# Quadcopter.net
KiCad netlist of a schematic drawn in EAGLE
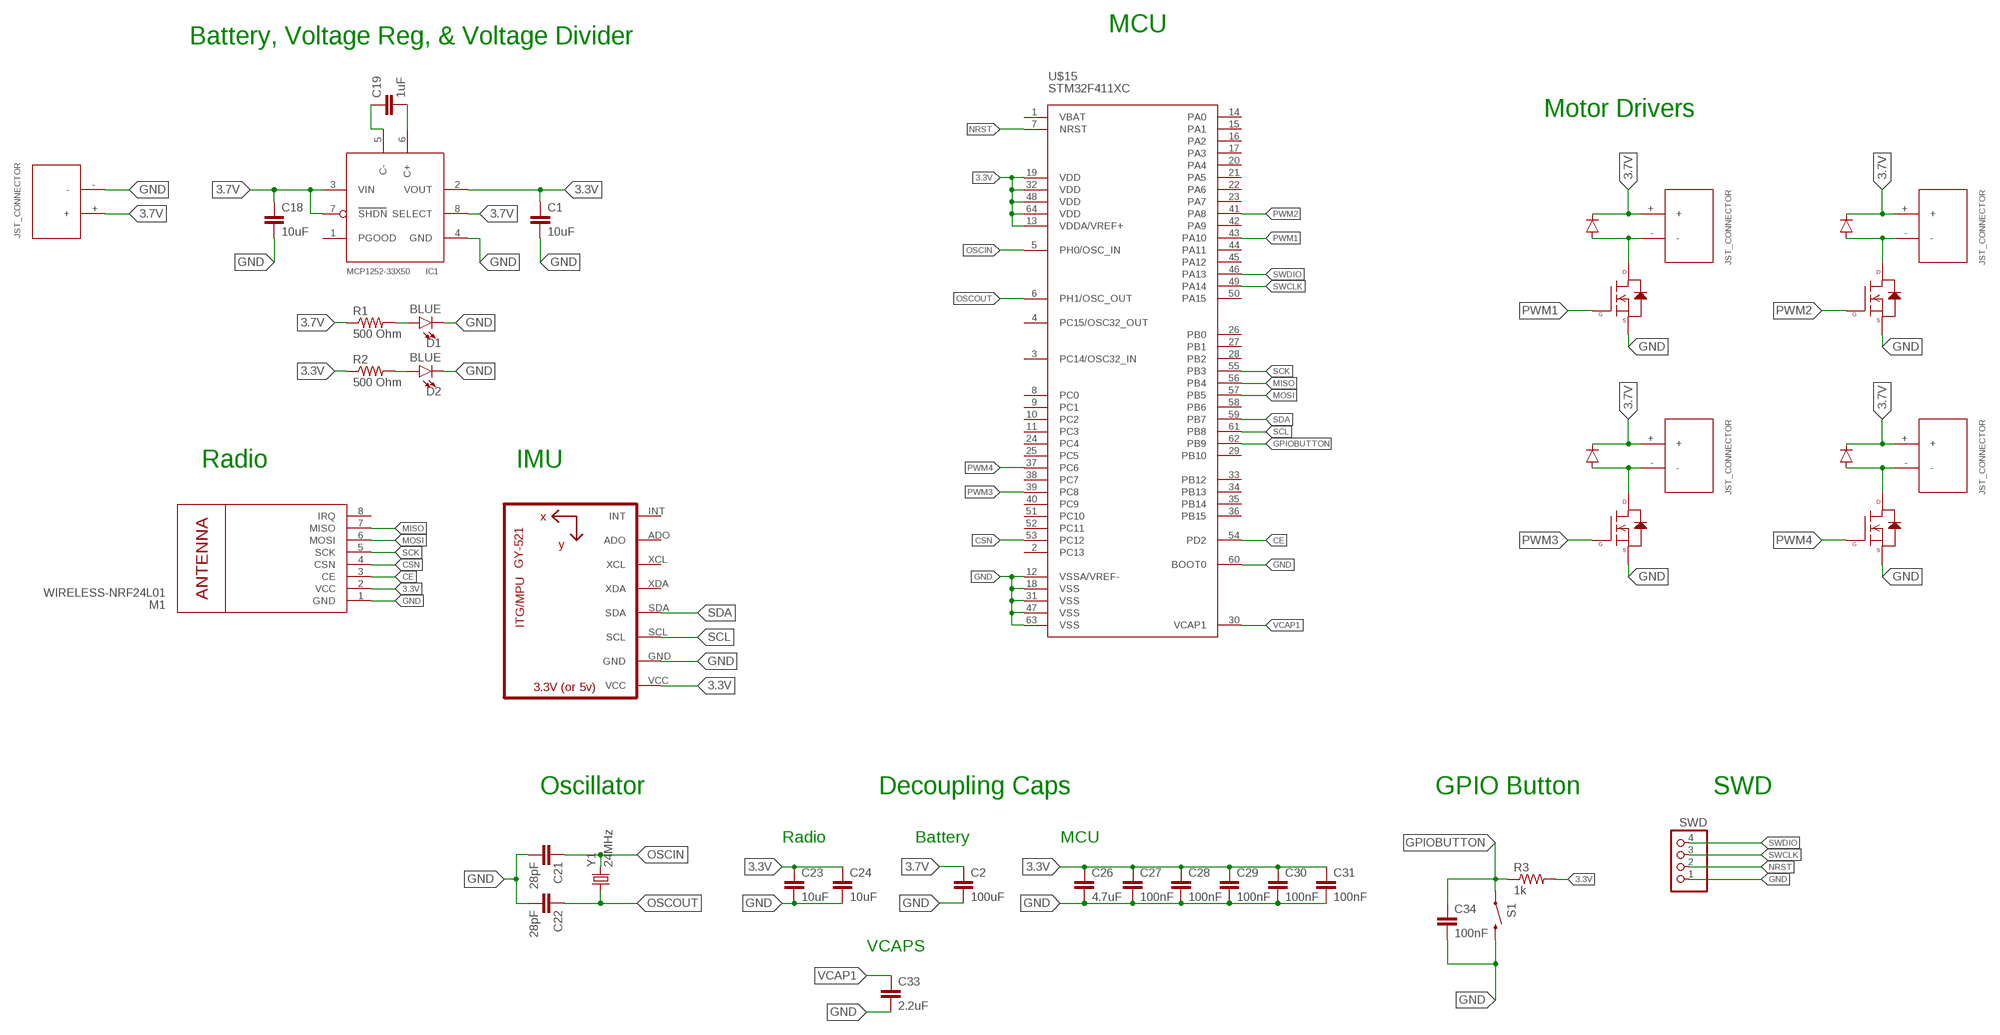
[diagram p0: schematic, sheet 1]

(export (version "E")
  (design (tool "Eeschema 10.0.6"))
  (components
    (comp (ref "C1")
      (value "10uF")
      (footprint "eagle-import:C0402K")
      (libsource (lib "eagle-import") (part "C-EUC0402K"))
    )
    (comp (ref "C2")
      (value "100uF")
      (footprint "eagle-import:C1206")
      (libsource (lib "eagle-import") (part "C-EUC1206"))
    )
    (comp (ref "C18")
      (value "10uF")
      (footprint "eagle-import:C0402K")
      (libsource (lib "eagle-import") (part "C-EUC0402K"))
    )
    (comp (ref "C19")
      (value "1uF")
      (footprint "eagle-import:C0402K")
      (libsource (lib "eagle-import") (part "C-EUC0402K"))
    )
    (comp (ref "C21")
      (value "28pF")
      (footprint "eagle-import:C0402K")
      (libsource (lib "eagle-import") (part "C-EUC0402K"))
    )
    (comp (ref "C22")
      (value "28pF")
      (footprint "eagle-import:C0402K")
      (libsource (lib "eagle-import") (part "C-EUC0402K"))
    )
    (comp (ref "C23")
      (value "10uF")
      (footprint "eagle-import:C0402K")
      (libsource (lib "eagle-import") (part "C-EUC0402K"))
    )
    (comp (ref "C24")
      (value "10uF")
      (footprint "eagle-import:C0402K")
      (libsource (lib "eagle-import") (part "C-EUC0402K"))
    )
    (comp (ref "C26")
      (value "4.7uF")
      (footprint "eagle-import:C0402K")
      (libsource (lib "eagle-import") (part "C-EUC0402K"))
    )
    (comp (ref "C27")
      (value "100nF")
      (footprint "eagle-import:C0402K")
      (libsource (lib "eagle-import") (part "C-EUC0402K"))
    )
    (comp (ref "C28")
      (value "100nF")
      (footprint "eagle-import:C0402K")
      (libsource (lib "eagle-import") (part "C-EUC0402K"))
    )
    (comp (ref "C29")
      (value "100nF")
      (footprint "eagle-import:C0402K")
      (libsource (lib "eagle-import") (part "C-EUC0402K"))
    )
    (comp (ref "C30")
      (value "100nF")
      (footprint "eagle-import:C0402K")
      (libsource (lib "eagle-import") (part "C-EUC0402K"))
    )
    (comp (ref "C31")
      (value "100nF")
      (footprint "eagle-import:C0402K")
      (libsource (lib "eagle-import") (part "C-EUC0402K"))
    )
    (comp (ref "C33")
      (value "2.2uF")
      (footprint "eagle-import:C0402K")
      (libsource (lib "eagle-import") (part "C-EUC0402K"))
    )
    (comp (ref "C34")
      (value "100nF")
      (footprint "eagle-import:C0402K")
      (libsource (lib "eagle-import") (part "C-EUC0402K"))
    )
    (comp (ref "D1")
      (value "BLUE")
      (footprint "eagle-import:LED-0603")
      (libsource (lib "eagle-import") (part "LED-BLUE0603"))
    )
    (comp (ref "D2")
      (value "BLUE")
      (footprint "eagle-import:LED-0603")
      (libsource (lib "eagle-import") (part "LED-BLUE0603"))
    )
    (comp (ref "IC1")
      (value "MCP1252-33X50")
      (footprint "eagle-import:MSOP8")
      (libsource (lib "eagle-import") (part "MCP1252-33X50"))
    )
    (comp (ref "JP1")
      (value "SWD")
      (footprint "eagle-import:1X04")
      (libsource (lib "eagle-import") (part "PINHD-1X4"))
    )
    (comp (ref "M1")
      (value "WIRELESS-NRF24L01")
      (footprint "eagle-import:WIRELESS-NRF24L01")
      (libsource (lib "eagle-import") (part "WIRELESS-NRF24L01"))
    )
    (comp (ref "R1")
      (value "500 Ohm")
      (footprint "eagle-import:R0402")
      (libsource (lib "eagle-import") (part "R-US_R0402"))
    )
    (comp (ref "R2")
      (value "500 Ohm")
      (footprint "eagle-import:R0402")
      (libsource (lib "eagle-import") (part "R-US_R0402"))
    )
    (comp (ref "R3")
      (value "1k")
      (footprint "eagle-import:R0402")
      (libsource (lib "eagle-import") (part "R-US_R0402"))
    )
    (comp (ref "S1")
      (value "SWITCH-MOMENTARY-2SMD")
      (footprint "eagle-import:TACTILE-SWITCH-SMD")
      (libsource (lib "eagle-import") (part "SWITCH-MOMENTARY-2SMD"))
    )
    (comp (ref "U$2")
      (value "JST_CONNECTOR_FEMALE")
      (footprint "eagle-import:JST_CONNECTOR_FEMALE")
      (libsource (lib "eagle-import") (part "JST_CONNECTOR_FEMALE"))
    )
    (comp (ref "U$3")
      (value "JST_CONNECTOR_FEMALE")
      (footprint "eagle-import:JST_CONNECTOR_FEMALE")
      (libsource (lib "eagle-import") (part "JST_CONNECTOR_FEMALE"))
    )
    (comp (ref "U$4")
      (value "JST_CONNECTOR_FEMALE")
      (footprint "eagle-import:JST_CONNECTOR_FEMALE")
      (libsource (lib "eagle-import") (part "JST_CONNECTOR_FEMALE"))
    )
    (comp (ref "U$5")
      (value "N-CHANNEL-MOSFET-IRLML6244TRPBF")
      (footprint "eagle-import:SOT23-3")
      (libsource (lib "eagle-import") (part "N-CHANNEL-MOSFET-IRLML6244TRPBF"))
    )
    (comp (ref "U$6")
      (value "DB2W40300L")
      (footprint "eagle-import:MINI2-F3-B")
      (libsource (lib "eagle-import") (part "DB2W40300L"))
    )
    (comp (ref "U$7")
      (value "JST_CONNECTOR_FEMALE")
      (footprint "eagle-import:JST_CONNECTOR_FEMALE")
      (libsource (lib "eagle-import") (part "JST_CONNECTOR_FEMALE"))
    )
    (comp (ref "U$8")
      (value "N-CHANNEL-MOSFET-IRLML6244TRPBF")
      (footprint "eagle-import:SOT23-3")
      (libsource (lib "eagle-import") (part "N-CHANNEL-MOSFET-IRLML6244TRPBF"))
    )
    (comp (ref "U$9")
      (value "DB2W40300L")
      (footprint "eagle-import:MINI2-F3-B")
      (libsource (lib "eagle-import") (part "DB2W40300L"))
    )
    (comp (ref "U$10")
      (value "N-CHANNEL-MOSFET-IRLML6244TRPBF")
      (footprint "eagle-import:SOT23-3")
      (libsource (lib "eagle-import") (part "N-CHANNEL-MOSFET-IRLML6244TRPBF"))
    )
    (comp (ref "U$11")
      (value "JST_CONNECTOR_FEMALE")
      (footprint "eagle-import:JST_CONNECTOR_FEMALE")
      (libsource (lib "eagle-import") (part "JST_CONNECTOR_FEMALE"))
    )
    (comp (ref "U$12")
      (value "N-CHANNEL-MOSFET-IRLML6244TRPBF")
      (footprint "eagle-import:SOT23-3")
      (libsource (lib "eagle-import") (part "N-CHANNEL-MOSFET-IRLML6244TRPBF"))
    )
    (comp (ref "U$13")
      (value "DB2W40300L")
      (footprint "eagle-import:MINI2-F3-B")
      (libsource (lib "eagle-import") (part "DB2W40300L"))
    )
    (comp (ref "U$14")
      (value "DB2W40300L")
      (footprint "eagle-import:MINI2-F3-B")
      (libsource (lib "eagle-import") (part "DB2W40300L"))
    )
    (comp (ref "U$15")
      (value "STM32F411XC")
      (footprint "eagle-import:LQFP64")
      (libsource (lib "eagle-import") (part "STM32F411XC"))
    )
    (comp (ref "U1")
      (value "GY-521MPU6050")
      (footprint "eagle-import:GY-521")
      (libsource (lib "eagle-import") (part "GY-521MPU6050"))
    )
    (comp (ref "Y1")
      (value "24MHz")
      (footprint "eagle-import:HC49UP")
      (libsource (lib "eagle-import") (part "CRYSTALSMD"))
    )
  )
  (nets
    (net (code "1") (name "3.3V") (class "Default")
      (node (ref "C1") (pin "1") (pinfunction "1_1") (pintype "passive"))
      (node (ref "C23") (pin "1") (pinfunction "1_1") (pintype "passive"))
      (node (ref "C24") (pin "1") (pinfunction "1_1") (pintype "passive"))
      (node (ref "C26") (pin "1") (pinfunction "1_1") (pintype "passive"))
      (node (ref "C27") (pin "1") (pinfunction "1_1") (pintype "passive"))
      (node (ref "C28") (pin "1") (pinfunction "1_1") (pintype "passive"))
      (node (ref "C29") (pin "1") (pinfunction "1_1") (pintype "passive"))
      (node (ref "C30") (pin "1") (pinfunction "1_1") (pintype "passive"))
      (node (ref "C31") (pin "1") (pinfunction "1_1") (pintype "passive"))
      (node (ref "IC1") (pin "2") (pinfunction "VOUT_2") (pintype "output"))
      (node (ref "M1") (pin "2") (pinfunction "VCC_2") (pintype "power_in"))
      (node (ref "R2") (pin "1") (pinfunction "1_1") (pintype "passive"))
      (node (ref "R3") (pin "2") (pinfunction "2_2") (pintype "passive"))
      (node (ref "U$15") (pin "13") (pinfunction "VDDA/VREF+_13") (pintype "bidirectional"))
      (node (ref "U$15") (pin "19") (pinfunction "VDD_19") (pintype "bidirectional"))
      (node (ref "U$15") (pin "32") (pinfunction "VDD_32") (pintype "bidirectional"))
      (node (ref "U$15") (pin "48") (pinfunction "VDD_48") (pintype "bidirectional"))
      (node (ref "U$15") (pin "64") (pinfunction "VDD_64") (pintype "bidirectional"))
      (node (ref "U1") (pin "VCC") (pinfunction "VCC_VCC") (pintype "bidirectional"))
    )
    (net (code "2") (name "3.7V") (class "Default")
      (node (ref "C18") (pin "1") (pinfunction "1_1") (pintype "passive"))
      (node (ref "C2") (pin "1") (pinfunction "1_1") (pintype "passive"))
      (node (ref "IC1") (pin "3") (pinfunction "VIN_3") (pintype "power_in"))
      (node (ref "IC1") (pin "7") (pinfunction "SHDN_7") (pintype "input"))
      (node (ref "IC1") (pin "8") (pinfunction "SELECT_8") (pintype "input"))
      (node (ref "R1") (pin "1") (pinfunction "1_1") (pintype "passive"))
      (node (ref "U$11") (pin "+") (pinfunction "+_+") (pintype "bidirectional"))
      (node (ref "U$13") (pin "NEG") (pinfunction "GPIN_NEG") (pintype "passive"))
      (node (ref "U$14") (pin "NEG") (pinfunction "GPIN_NEG") (pintype "passive"))
      (node (ref "U$2") (pin "+") (pinfunction "+_+") (pintype "bidirectional"))
      (node (ref "U$3") (pin "+") (pinfunction "+_+") (pintype "bidirectional"))
      (node (ref "U$4") (pin "+") (pinfunction "+_+") (pintype "bidirectional"))
      (node (ref "U$6") (pin "NEG") (pinfunction "GPIN_NEG") (pintype "passive"))
      (node (ref "U$7") (pin "+") (pinfunction "+_+") (pintype "bidirectional"))
      (node (ref "U$9") (pin "NEG") (pinfunction "GPIN_NEG") (pintype "passive"))
    )
    (net (code "3") (name "CE") (class "Default")
      (node (ref "M1") (pin "3") (pinfunction "CE_3") (pintype "bidirectional"))
      (node (ref "U$15") (pin "54") (pinfunction "PD2_54") (pintype "bidirectional"))
    )
    (net (code "4") (name "CSN") (class "Default")
      (node (ref "M1") (pin "4") (pinfunction "CSN_4") (pintype "bidirectional"))
      (node (ref "U$15") (pin "53") (pinfunction "PC12_53") (pintype "bidirectional"))
    )
    (net (code "5") (name "GND") (class "Default")
      (node (ref "C1") (pin "2") (pinfunction "2_2") (pintype "passive"))
      (node (ref "C18") (pin "2") (pinfunction "2_2") (pintype "passive"))
      (node (ref "C2") (pin "2") (pinfunction "2_2") (pintype "passive"))
      (node (ref "C21") (pin "2") (pinfunction "2_2") (pintype "passive"))
      (node (ref "C22") (pin "2") (pinfunction "2_2") (pintype "passive"))
      (node (ref "C23") (pin "2") (pinfunction "2_2") (pintype "passive"))
      (node (ref "C24") (pin "2") (pinfunction "2_2") (pintype "passive"))
      (node (ref "C26") (pin "2") (pinfunction "2_2") (pintype "passive"))
      (node (ref "C27") (pin "2") (pinfunction "2_2") (pintype "passive"))
      (node (ref "C28") (pin "2") (pinfunction "2_2") (pintype "passive"))
      (node (ref "C29") (pin "2") (pinfunction "2_2") (pintype "passive"))
      (node (ref "C30") (pin "2") (pinfunction "2_2") (pintype "passive"))
      (node (ref "C31") (pin "2") (pinfunction "2_2") (pintype "passive"))
      (node (ref "C33") (pin "2") (pinfunction "2_2") (pintype "passive"))
      (node (ref "C34") (pin "2") (pinfunction "2_2") (pintype "passive"))
      (node (ref "D1") (pin "C") (pinfunction "C_C") (pintype "passive"))
      (node (ref "D2") (pin "C") (pinfunction "C_C") (pintype "passive"))
      (node (ref "IC1") (pin "4") (pinfunction "GND_4") (pintype "power_in"))
      (node (ref "JP1") (pin "1") (pinfunction "1_1") (pintype "passive"))
      (node (ref "M1") (pin "1") (pinfunction "GND_1") (pintype "power_in"))
      (node (ref "S1") (pin "3") (pinfunction "2_3") (pintype "passive"))
      (node (ref "U$10") (pin "2") (pinfunction "S_2") (pintype "passive"))
      (node (ref "U$12") (pin "2") (pinfunction "S_2") (pintype "passive"))
      (node (ref "U$15") (pin "12") (pinfunction "VSSA/VREF-_12") (pintype "bidirectional"))
      (node (ref "U$15") (pin "18") (pinfunction "VSS_18") (pintype "bidirectional"))
      (node (ref "U$15") (pin "31") (pinfunction "VSS_31") (pintype "bidirectional"))
      (node (ref "U$15") (pin "47") (pinfunction "VSS_47") (pintype "bidirectional"))
      (node (ref "U$15") (pin "60") (pinfunction "BOOT0_60") (pintype "bidirectional"))
      (node (ref "U$15") (pin "63") (pinfunction "VSS_63") (pintype "bidirectional"))
      (node (ref "U$3") (pin "-") (pinfunction "-_-") (pintype "bidirectional"))
      (node (ref "U$5") (pin "2") (pinfunction "S_2") (pintype "passive"))
      (node (ref "U$8") (pin "2") (pinfunction "S_2") (pintype "passive"))
      (node (ref "U1") (pin "GND") (pinfunction "GND_GND") (pintype "bidirectional"))
    )
    (net (code "6") (name "GPIOBUTTON") (class "Default")
      (node (ref "C34") (pin "1") (pinfunction "1_1") (pintype "passive"))
      (node (ref "R3") (pin "1") (pinfunction "1_1") (pintype "passive"))
      (node (ref "S1") (pin "1") (pinfunction "1_1") (pintype "passive"))
      (node (ref "U$15") (pin "62") (pinfunction "PB9_62") (pintype "bidirectional"))
    )
    (net (code "7") (name "MISO") (class "Default")
      (node (ref "M1") (pin "7") (pinfunction "MISO_7") (pintype "bidirectional"))
      (node (ref "U$15") (pin "56") (pinfunction "PB4_56") (pintype "bidirectional"))
    )
    (net (code "8") (name "MOSI") (class "Default")
      (node (ref "M1") (pin "6") (pinfunction "MOSI_6") (pintype "bidirectional"))
      (node (ref "U$15") (pin "57") (pinfunction "PB5_57") (pintype "bidirectional"))
    )
    (net (code "9") (name "NRST") (class "Default")
      (node (ref "JP1") (pin "2") (pinfunction "2_2") (pintype "passive"))
      (node (ref "U$15") (pin "7") (pinfunction "NRST_7") (pintype "bidirectional"))
    )
    (net (code "10") (name "Net-(D1-PadA)") (class "Default")
      (node (ref "D1") (pin "A") (pinfunction "A_A") (pintype "passive"))
      (node (ref "R1") (pin "2") (pinfunction "2_2") (pintype "passive"))
    )
    (net (code "11") (name "Net-(D2-PadA)") (class "Default")
      (node (ref "D2") (pin "A") (pinfunction "A_A") (pintype "passive"))
      (node (ref "R2") (pin "2") (pinfunction "2_2") (pintype "passive"))
    )
    (net (code "12") (name "Net-(IC1-C+)") (class "Default")
      (node (ref "C19") (pin "2") (pinfunction "2_2") (pintype "passive"))
      (node (ref "IC1") (pin "6") (pinfunction "C+_6") (pintype "passive"))
    )
    (net (code "13") (name "Net-(IC1-C-)") (class "Default")
      (node (ref "C19") (pin "1") (pinfunction "1_1") (pintype "passive"))
      (node (ref "IC1") (pin "5") (pinfunction "C-_5") (pintype "passive"))
    )
    (net (code "14") (name "Net-(U$5-D)") (class "Default")
      (node (ref "U$2") (pin "-") (pinfunction "-_-") (pintype "bidirectional"))
      (node (ref "U$5") (pin "3") (pinfunction "D_3") (pintype "passive"))
      (node (ref "U$6") (pin "POS") (pinfunction "PPIN_POS") (pintype "passive"))
    )
    (net (code "15") (name "Net-(U$8-D)") (class "Default")
      (node (ref "U$7") (pin "-") (pinfunction "-_-") (pintype "bidirectional"))
      (node (ref "U$8") (pin "3") (pinfunction "D_3") (pintype "passive"))
      (node (ref "U$9") (pin "POS") (pinfunction "PPIN_POS") (pintype "passive"))
    )
    (net (code "16") (name "Net-(U$10-D)") (class "Default")
      (node (ref "U$10") (pin "3") (pinfunction "D_3") (pintype "passive"))
      (node (ref "U$14") (pin "POS") (pinfunction "PPIN_POS") (pintype "passive"))
      (node (ref "U$4") (pin "-") (pinfunction "-_-") (pintype "bidirectional"))
    )
    (net (code "17") (name "Net-(U$12-D)") (class "Default")
      (node (ref "U$11") (pin "-") (pinfunction "-_-") (pintype "bidirectional"))
      (node (ref "U$12") (pin "3") (pinfunction "D_3") (pintype "passive"))
      (node (ref "U$13") (pin "POS") (pinfunction "PPIN_POS") (pintype "passive"))
    )
    (net (code "18") (name "OSCIN") (class "Default")
      (node (ref "C21") (pin "1") (pinfunction "1_1") (pintype "passive"))
      (node (ref "U$15") (pin "5") (pinfunction "PH0/OSC_IN_5") (pintype "bidirectional"))
      (node (ref "Y1") (pin "2") (pinfunction "2_2") (pintype "passive"))
    )
    (net (code "19") (name "OSCOUT") (class "Default")
      (node (ref "C22") (pin "1") (pinfunction "1_1") (pintype "passive"))
      (node (ref "U$15") (pin "6") (pinfunction "PH1/OSC_OUT_6") (pintype "bidirectional"))
      (node (ref "Y1") (pin "1") (pinfunction "1_1") (pintype "passive"))
    )
    (net (code "20") (name "PWM1") (class "Default")
      (node (ref "U$10") (pin "1") (pinfunction "G_1") (pintype "passive"))
      (node (ref "U$15") (pin "43") (pinfunction "PA10_43") (pintype "bidirectional"))
    )
    (net (code "21") (name "PWM2") (class "Default")
      (node (ref "U$15") (pin "41") (pinfunction "PA8_41") (pintype "bidirectional"))
      (node (ref "U$5") (pin "1") (pinfunction "G_1") (pintype "passive"))
    )
    (net (code "22") (name "PWM3") (class "Default")
      (node (ref "U$15") (pin "39") (pinfunction "PC8_39") (pintype "bidirectional"))
      (node (ref "U$8") (pin "1") (pinfunction "G_1") (pintype "passive"))
    )
    (net (code "23") (name "PWM4") (class "Default")
      (node (ref "U$12") (pin "1") (pinfunction "G_1") (pintype "passive"))
      (node (ref "U$15") (pin "37") (pinfunction "PC6_37") (pintype "bidirectional"))
    )
    (net (code "24") (name "SCK") (class "Default")
      (node (ref "M1") (pin "5") (pinfunction "SCK_5") (pintype "bidirectional"))
      (node (ref "U$15") (pin "55") (pinfunction "PB3_55") (pintype "bidirectional"))
    )
    (net (code "25") (name "SCL") (class "Default")
      (node (ref "U$15") (pin "61") (pinfunction "PB8_61") (pintype "bidirectional"))
      (node (ref "U1") (pin "SCL") (pinfunction "SCL_SCL") (pintype "bidirectional"))
    )
    (net (code "26") (name "SDA") (class "Default")
      (node (ref "U$15") (pin "59") (pinfunction "PB7_59") (pintype "bidirectional"))
      (node (ref "U1") (pin "SDA") (pinfunction "SDA_SDA") (pintype "bidirectional"))
    )
    (net (code "27") (name "SWCLK") (class "Default")
      (node (ref "JP1") (pin "3") (pinfunction "3_3") (pintype "passive"))
      (node (ref "U$15") (pin "49") (pinfunction "PA14_49") (pintype "bidirectional"))
    )
    (net (code "28") (name "SWDIO") (class "Default")
      (node (ref "JP1") (pin "4") (pinfunction "4_4") (pintype "passive"))
      (node (ref "U$15") (pin "46") (pinfunction "PA13_46") (pintype "bidirectional"))
    )
    (net (code "29") (name "VCAP1") (class "Default")
      (node (ref "C33") (pin "1") (pinfunction "1_1") (pintype "passive"))
      (node (ref "U$15") (pin "30") (pinfunction "VCAP1_30") (pintype "bidirectional"))
    )
    (net (code "30") (name "unconnected-(IC1-PGOOD-Pad1)") (class "Default")
      (node (ref "IC1") (pin "1") (pinfunction "PGOOD_1") (pintype "output"))
    )
    (net (code "31") (name "unconnected-(M1-IRQ-Pad8)") (class "Default")
      (node (ref "M1") (pin "8") (pinfunction "IRQ_8") (pintype "bidirectional"))
    )
    (net (code "32") (name "unconnected-(U$15-PA0-Pad14)") (class "Default")
      (node (ref "U$15") (pin "14") (pinfunction "PA0_14") (pintype "bidirectional"))
    )
    (net (code "33") (name "unconnected-(U$15-PA1-Pad15)") (class "Default")
      (node (ref "U$15") (pin "15") (pinfunction "PA1_15") (pintype "bidirectional"))
    )
    (net (code "34") (name "unconnected-(U$15-PA2-Pad16)") (class "Default")
      (node (ref "U$15") (pin "16") (pinfunction "PA2_16") (pintype "bidirectional"))
    )
    (net (code "35") (name "unconnected-(U$15-PA3-Pad17)") (class "Default")
      (node (ref "U$15") (pin "17") (pinfunction "PA3_17") (pintype "bidirectional"))
    )
    (net (code "36") (name "unconnected-(U$15-PA4-Pad20)") (class "Default")
      (node (ref "U$15") (pin "20") (pinfunction "PA4_20") (pintype "bidirectional"))
    )
    (net (code "37") (name "unconnected-(U$15-PA5-Pad21)") (class "Default")
      (node (ref "U$15") (pin "21") (pinfunction "PA5_21") (pintype "bidirectional"))
    )
    (net (code "38") (name "unconnected-(U$15-PA6-Pad22)") (class "Default")
      (node (ref "U$15") (pin "22") (pinfunction "PA6_22") (pintype "bidirectional"))
    )
    (net (code "39") (name "unconnected-(U$15-PA7-Pad23)") (class "Default")
      (node (ref "U$15") (pin "23") (pinfunction "PA7_23") (pintype "bidirectional"))
    )
    (net (code "40") (name "unconnected-(U$15-PA9-Pad42)") (class "Default")
      (node (ref "U$15") (pin "42") (pinfunction "PA9_42") (pintype "bidirectional"))
    )
    (net (code "41") (name "unconnected-(U$15-PA11-Pad44)") (class "Default")
      (node (ref "U$15") (pin "44") (pinfunction "PA11_44") (pintype "bidirectional"))
    )
    (net (code "42") (name "unconnected-(U$15-PA12-Pad45)") (class "Default")
      (node (ref "U$15") (pin "45") (pinfunction "PA12_45") (pintype "bidirectional"))
    )
    (net (code "43") (name "unconnected-(U$15-PA15-Pad50)") (class "Default")
      (node (ref "U$15") (pin "50") (pinfunction "PA15_50") (pintype "bidirectional"))
    )
    (net (code "44") (name "unconnected-(U$15-PB0-Pad26)") (class "Default")
      (node (ref "U$15") (pin "26") (pinfunction "PB0_26") (pintype "bidirectional"))
    )
    (net (code "45") (name "unconnected-(U$15-PB1-Pad27)") (class "Default")
      (node (ref "U$15") (pin "27") (pinfunction "PB1_27") (pintype "bidirectional"))
    )
    (net (code "46") (name "unconnected-(U$15-PB2-Pad28)") (class "Default")
      (node (ref "U$15") (pin "28") (pinfunction "PB2_28") (pintype "bidirectional"))
    )
    (net (code "47") (name "unconnected-(U$15-PB6-Pad58)") (class "Default")
      (node (ref "U$15") (pin "58") (pinfunction "PB6_58") (pintype "bidirectional"))
    )
    (net (code "48") (name "unconnected-(U$15-PB10-Pad29)") (class "Default")
      (node (ref "U$15") (pin "29") (pinfunction "PB10_29") (pintype "bidirectional"))
    )
    (net (code "49") (name "unconnected-(U$15-PB12-Pad33)") (class "Default")
      (node (ref "U$15") (pin "33") (pinfunction "PB12_33") (pintype "bidirectional"))
    )
    (net (code "50") (name "unconnected-(U$15-PB13-Pad34)") (class "Default")
      (node (ref "U$15") (pin "34") (pinfunction "PB13_34") (pintype "bidirectional"))
    )
    (net (code "51") (name "unconnected-(U$15-PB14-Pad35)") (class "Default")
      (node (ref "U$15") (pin "35") (pinfunction "PB14_35") (pintype "bidirectional"))
    )
    (net (code "52") (name "unconnected-(U$15-PB15-Pad36)") (class "Default")
      (node (ref "U$15") (pin "36") (pinfunction "PB15_36") (pintype "bidirectional"))
    )
    (net (code "53") (name "unconnected-(U$15-PC0-Pad8)") (class "Default")
      (node (ref "U$15") (pin "8") (pinfunction "PC0_8") (pintype "bidirectional"))
    )
    (net (code "54") (name "unconnected-(U$15-PC1-Pad9)") (class "Default")
      (node (ref "U$15") (pin "9") (pinfunction "PC1_9") (pintype "bidirectional"))
    )
    (net (code "55") (name "unconnected-(U$15-PC2-Pad10)") (class "Default")
      (node (ref "U$15") (pin "10") (pinfunction "PC2_10") (pintype "bidirectional"))
    )
    (net (code "56") (name "unconnected-(U$15-PC3-Pad11)") (class "Default")
      (node (ref "U$15") (pin "11") (pinfunction "PC3_11") (pintype "bidirectional"))
    )
    (net (code "57") (name "unconnected-(U$15-PC4-Pad24)") (class "Default")
      (node (ref "U$15") (pin "24") (pinfunction "PC4_24") (pintype "bidirectional"))
    )
    (net (code "58") (name "unconnected-(U$15-PC5-Pad25)") (class "Default")
      (node (ref "U$15") (pin "25") (pinfunction "PC5_25") (pintype "bidirectional"))
    )
    (net (code "59") (name "unconnected-(U$15-PC7-Pad38)") (class "Default")
      (node (ref "U$15") (pin "38") (pinfunction "PC7_38") (pintype "bidirectional"))
    )
    (net (code "60") (name "unconnected-(U$15-PC9-Pad40)") (class "Default")
      (node (ref "U$15") (pin "40") (pinfunction "PC9_40") (pintype "bidirectional"))
    )
    (net (code "61") (name "unconnected-(U$15-PC10-Pad51)") (class "Default")
      (node (ref "U$15") (pin "51") (pinfunction "PC10_51") (pintype "bidirectional"))
    )
    (net (code "62") (name "unconnected-(U$15-PC11-Pad52)") (class "Default")
      (node (ref "U$15") (pin "52") (pinfunction "PC11_52") (pintype "bidirectional"))
    )
    (net (code "63") (name "unconnected-(U$15-PC13-Pad2)") (class "Default")
      (node (ref "U$15") (pin "2") (pinfunction "PC13_2") (pintype "bidirectional"))
    )
    (net (code "64") (name "unconnected-(U$15-PC14{slash}OSC32_IN-Pad3)") (class "Default")
      (node (ref "U$15") (pin "3") (pinfunction "PC14/OSC32_IN_3") (pintype "bidirectional"))
    )
    (net (code "65") (name "unconnected-(U$15-PC15{slash}OSC32_OUT-Pad4)") (class "Default")
      (node (ref "U$15") (pin "4") (pinfunction "PC15/OSC32_OUT_4") (pintype "bidirectional"))
    )
    (net (code "66") (name "unconnected-(U$15-VBAT-Pad1)") (class "Default")
      (node (ref "U$15") (pin "1") (pinfunction "VBAT_1") (pintype "bidirectional"))
    )
    (net (code "67") (name "unconnected-(U1-PadADO)") (class "Default")
      (node (ref "U1") (pin "ADO") (pinfunction "ADO_ADO") (pintype "bidirectional"))
    )
    (net (code "68") (name "unconnected-(U1-PadINT)") (class "Default")
      (node (ref "U1") (pin "INT") (pinfunction "INT_INT") (pintype "bidirectional"))
    )
    (net (code "69") (name "unconnected-(U1-PadXCL)") (class "Default")
      (node (ref "U1") (pin "XCL") (pinfunction "XCL_XCL") (pintype "bidirectional"))
    )
    (net (code "70") (name "unconnected-(U1-PadXDA)") (class "Default")
      (node (ref "U1") (pin "XDA") (pinfunction "XDA_XDA") (pintype "bidirectional"))
    )
  )
)
